# SCHematic_wetterstation_1_2021-12-09.net
KiCad netlist of a schematic drawn in EasyEDA
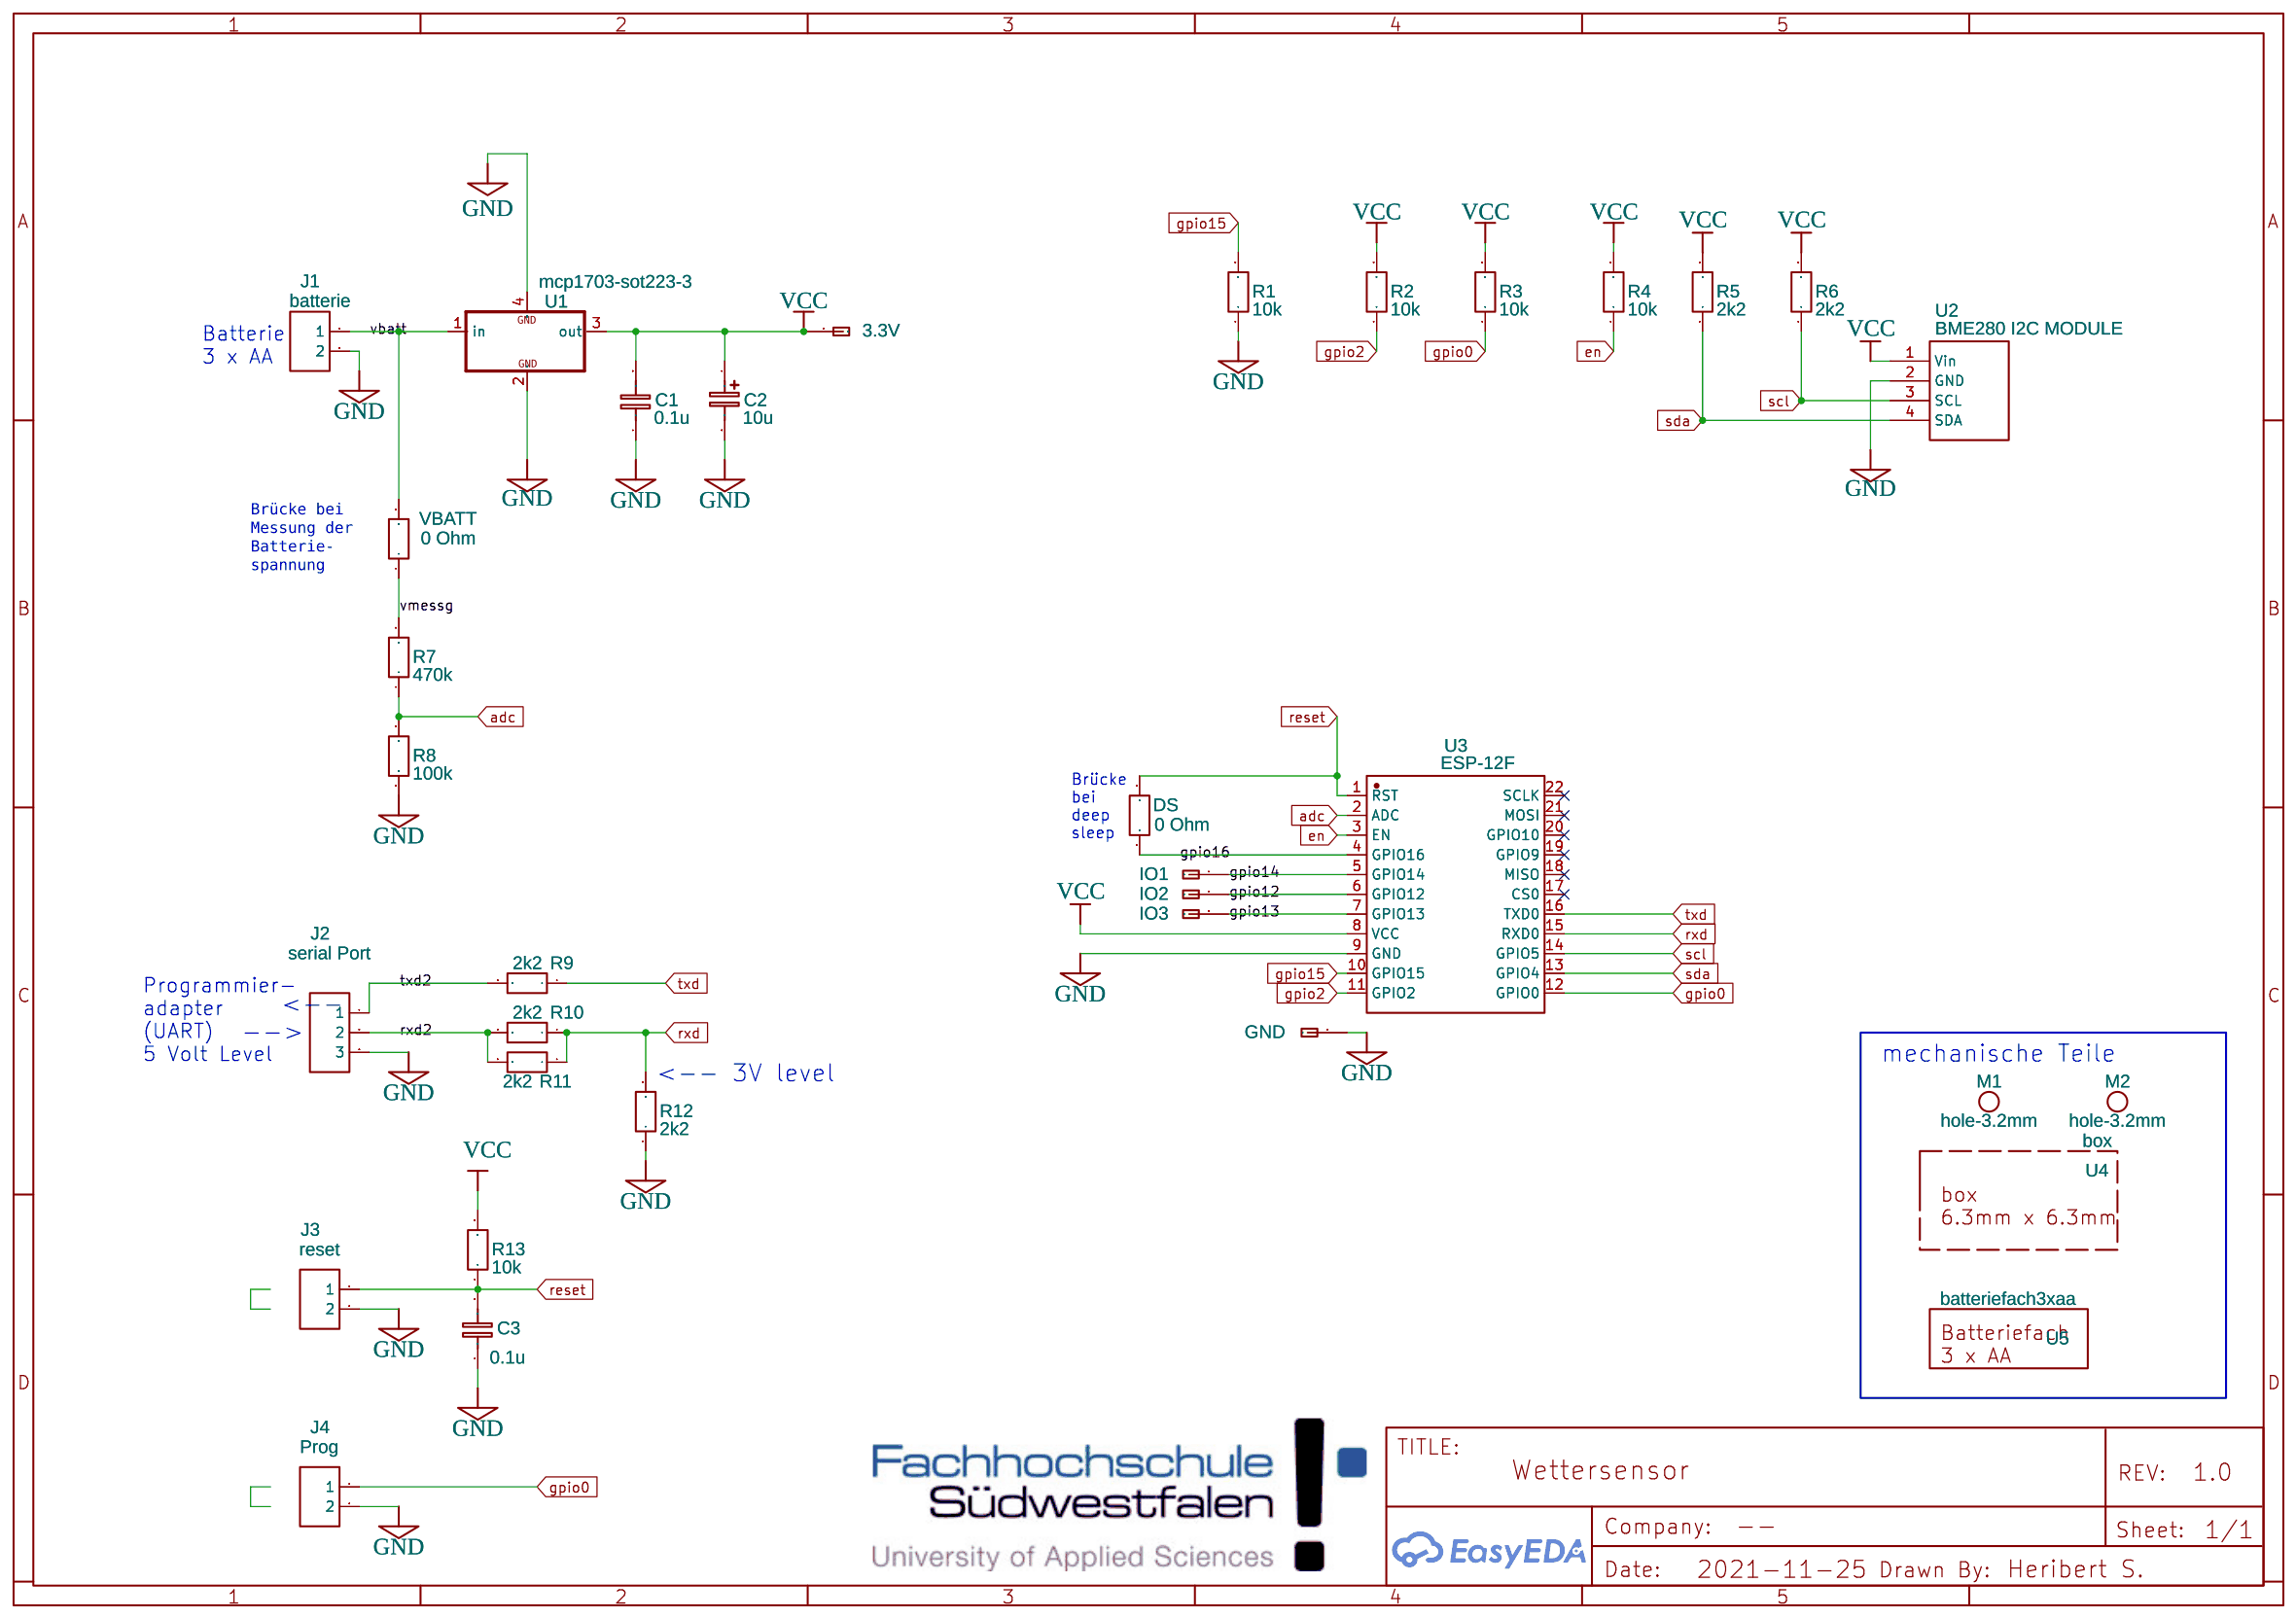
[diagram p0: schematic sheet]

(export (version "E")
  (design (tool "Eeschema 10.0.6"))
  (components
    (comp (ref "3.3V") (value "smdPad") (libsource (lib "") (part "smdPad_2")))
    (comp (ref "C1") (value "0.1u") (libsource (lib "") (part "C_0603_EU")))
    (comp (ref "C2") (value "10u") (libsource (lib "") (part "C_Tan_SMD_A_EU")))
    (comp (ref "C3") (value "0.1u") (libsource (lib "") (part "C_0603_EU_1")))
    (comp (ref "DS") (value "0 Ohm") (libsource (lib "") (part "R_0805_EU_3")))
    (comp (ref "GND") (value "smdPad") (libsource (lib "") (part "smdPad_1")))
    (comp (ref "IO1") (value "smdPad") (libsource (lib "") (part "smdPad")))
    (comp (ref "IO2") (value "smdPad") (libsource (lib "") (part "smdPad")))
    (comp (ref "IO3") (value "smdPad") (libsource (lib "") (part "smdPad")))
    (comp (ref "J1")
      (value "batterie")
      (fields (field (name "BOM_Supplier Part") "C124375"))
      (libsource (lib "") (part "HDR-M-2.54_1x2"))
    )
    (comp (ref "J2")
      (value "serial Port")
      (fields (field (name "BOM_Supplier Part") "C180248"))
      (libsource (lib "") (part "HDR-M-2.54_1x3"))
    )
    (comp (ref "J3")
      (value "reset")
      (fields (field (name "BOM_Supplier Part") "C124375"))
      (libsource (lib "") (part "HDR-M-2.54_1x2"))
    )
    (comp (ref "J4")
      (value "Prog")
      (fields (field (name "BOM_Supplier Part") "C124375"))
      (libsource (lib "") (part "HDR-M-2.54_1x2"))
    )
    (comp (ref "M1")
      (value "hole-3.2mm")
      (fields
        (field (name "BOM_Manufacturer Part") "SIN-002T-1.0")
        (field (name "BOM_Supplier Part") "C265414")
      )
      (libsource (lib "") (part "hole-3.2mm"))
    )
    (comp (ref "M2")
      (value "hole-3.2mm")
      (fields
        (field (name "BOM_Manufacturer Part") "SIN-002T-1.0")
        (field (name "BOM_Supplier Part") "C265414")
      )
      (libsource (lib "") (part "hole-3.2mm"))
    )
    (comp (ref "R1") (value "10k") (libsource (lib "") (part "R_0805_EU")))
    (comp (ref "R2") (value "10k") (libsource (lib "") (part "R_0805_EU")))
    (comp (ref "R3") (value "10k") (libsource (lib "") (part "R_0805_EU")))
    (comp (ref "R4") (value "10k") (libsource (lib "") (part "R_0805_EU")))
    (comp (ref "R5") (value "2k2") (libsource (lib "") (part "R_0805_EU")))
    (comp (ref "R6") (value "2k2") (libsource (lib "") (part "R_0805_EU")))
    (comp (ref "R7") (value "470k") (libsource (lib "") (part "R_0805_EU")))
    (comp (ref "R8") (value "100k") (libsource (lib "") (part "R_0805_EU")))
    (comp (ref "R9") (value "2k2") (libsource (lib "") (part "R_0805_EU_2")))
    (comp (ref "R10") (value "2k2") (libsource (lib "") (part "R_0805_EU_2")))
    (comp (ref "R11") (value "2k2") (libsource (lib "") (part "R_0805_EU_2")))
    (comp (ref "R12") (value "2k2") (libsource (lib "") (part "R_0805_EU")))
    (comp (ref "R13") (value "10k") (libsource (lib "") (part "R_0805_EU")))
    (comp (ref "U1")
      (value "mcp1703-sot223-3")
      (fields (field (name "BOM_Supplier Part") "MCP 1703-3302"))
      (libsource (lib "") (part "mcp1703-sot223-3"))
    )
    (comp (ref "U2") (value "BME280 I2C MODULE") (libsource (lib "") (part "BME280 I2C MODULE")))
    (comp (ref "U3")
      (value "ESP-12F")
      (fields
        (field (name "BOM_Manufacturer Part") "ESP-12F(ESP8266MOD)")
        (field (name "BOM_Supplier Part") "C82891")
      )
      (libsource (lib "") (part "ESP-12F(ESP8266MOD)"))
    )
    (comp (ref "U4") (value "box") (libsource (lib "") (part "box")))
    (comp (ref "U5") (value "batteriefach3xaa") (libsource (lib "") (part "batteriefach3xaa")))
    (comp (ref "VBATT") (value "0 Ohm") (libsource (lib "") (part "R_0805_EU_1")))
  )
  (nets
    (net (code "1") (name "/gpio12") (class "Default")
      (node (ref "IO2") (pin "1") (pinfunction "1_1") (pintype "unspecified"))
      (node (ref "U3") (pin "6") (pinfunction "GPIO12_6") (pintype "unspecified"))
    )
    (net (code "2") (name "/gpio13") (class "Default")
      (node (ref "IO3") (pin "1") (pinfunction "1_1") (pintype "unspecified"))
      (node (ref "U3") (pin "7") (pinfunction "GPIO13_7") (pintype "unspecified"))
    )
    (net (code "3") (name "/gpio14") (class "Default")
      (node (ref "IO1") (pin "1") (pinfunction "1_1") (pintype "unspecified"))
      (node (ref "U3") (pin "5") (pinfunction "GPIO14_5") (pintype "unspecified"))
    )
    (net (code "4") (name "/gpio16") (class "Default")
      (node (ref "DS") (pin "1") (pinfunction "1_1") (pintype "unspecified"))
      (node (ref "U3") (pin "4") (pinfunction "GPIO16_4") (pintype "unspecified"))
    )
    (net (code "5") (name "/rxd2") (class "Default")
      (node (ref "J2") (pin "2") (pinfunction "2_2") (pintype "input"))
      (node (ref "R10") (pin "2") (pinfunction "2_2") (pintype "unspecified"))
      (node (ref "R11") (pin "2") (pinfunction "2_2") (pintype "unspecified"))
    )
    (net (code "6") (name "/txd2") (class "Default")
      (node (ref "J2") (pin "1") (pinfunction "1_1") (pintype "input"))
      (node (ref "R9") (pin "2") (pinfunction "2_2") (pintype "unspecified"))
    )
    (net (code "7") (name "/vbatt") (class "Default")
      (node (ref "J1") (pin "1") (pinfunction "1_1") (pintype "unspecified"))
      (node (ref "U1") (pin "1") (pinfunction "in_1") (pintype "bidirectional"))
      (node (ref "VBATT") (pin "2") (pinfunction "2_2") (pintype "unspecified"))
    )
    (net (code "8") (name "/vmessg") (class "Default")
      (node (ref "R7") (pin "2") (pinfunction "2_2") (pintype "unspecified"))
      (node (ref "VBATT") (pin "1") (pinfunction "1_1") (pintype "unspecified"))
    )
    (net (code "9") (name "GND") (class "Default")
      (node (ref "C1") (pin "1") (pinfunction "1_1") (pintype "unspecified"))
      (node (ref "C2") (pin "2") (pinfunction "2_2") (pintype "unspecified"))
      (node (ref "C3") (pin "1") (pinfunction "1_1") (pintype "unspecified"))
      (node (ref "GND") (pin "1") (pinfunction "1_1") (pintype "unspecified"))
      (node (ref "J1") (pin "2") (pinfunction "2_2") (pintype "unspecified"))
      (node (ref "J2") (pin "3") (pinfunction "3_3") (pintype "input"))
      (node (ref "J3") (pin "2") (pinfunction "2_2") (pintype "unspecified"))
      (node (ref "J4") (pin "2") (pinfunction "2_2") (pintype "unspecified"))
      (node (ref "R1") (pin "1") (pinfunction "1_1") (pintype "unspecified"))
      (node (ref "R12") (pin "1") (pinfunction "1_1") (pintype "unspecified"))
      (node (ref "R8") (pin "1") (pinfunction "1_1") (pintype "unspecified"))
      (node (ref "U1") (pin "2") (pinfunction "GND_2") (pintype "bidirectional"))
      (node (ref "U1") (pin "4") (pinfunction "GND_4") (pintype "bidirectional"))
      (node (ref "U2") (pin "2") (pinfunction "GND_2") (pintype "unspecified"))
      (node (ref "U3") (pin "9") (pinfunction "GND_9") (pintype "unspecified"))
    )
    (net (code "10") (name "VCC") (class "Default")
      (node (ref "3.3V") (pin "1") (pinfunction "1_1") (pintype "unspecified"))
      (node (ref "C1") (pin "2") (pinfunction "2_2") (pintype "unspecified"))
      (node (ref "C2") (pin "1") (pinfunction "1_1") (pintype "unspecified"))
      (node (ref "R13") (pin "2") (pinfunction "2_2") (pintype "unspecified"))
      (node (ref "R2") (pin "2") (pinfunction "2_2") (pintype "unspecified"))
      (node (ref "R3") (pin "2") (pinfunction "2_2") (pintype "unspecified"))
      (node (ref "R4") (pin "2") (pinfunction "2_2") (pintype "unspecified"))
      (node (ref "R5") (pin "2") (pinfunction "2_2") (pintype "unspecified"))
      (node (ref "R6") (pin "2") (pinfunction "2_2") (pintype "unspecified"))
      (node (ref "U1") (pin "3") (pinfunction "out_3") (pintype "bidirectional"))
      (node (ref "U2") (pin "1") (pinfunction "Vin_1") (pintype "unspecified"))
      (node (ref "U3") (pin "8") (pinfunction "VCC_8") (pintype "unspecified"))
    )
    (net (code "11") (name "adc") (class "Default")
      (node (ref "R7") (pin "1") (pinfunction "1_1") (pintype "unspecified"))
      (node (ref "R8") (pin "2") (pinfunction "2_2") (pintype "unspecified"))
      (node (ref "U3") (pin "2") (pinfunction "ADC_2") (pintype "unspecified"))
    )
    (net (code "12") (name "en") (class "Default")
      (node (ref "R4") (pin "1") (pinfunction "1_1") (pintype "unspecified"))
      (node (ref "U3") (pin "3") (pinfunction "EN_3") (pintype "unspecified"))
    )
    (net (code "13") (name "gpio0") (class "Default")
      (node (ref "J4") (pin "1") (pinfunction "1_1") (pintype "unspecified"))
      (node (ref "R3") (pin "1") (pinfunction "1_1") (pintype "unspecified"))
      (node (ref "U3") (pin "12") (pinfunction "GPIO0_12") (pintype "unspecified"))
    )
    (net (code "14") (name "gpio2") (class "Default")
      (node (ref "R2") (pin "1") (pinfunction "1_1") (pintype "unspecified"))
      (node (ref "U3") (pin "11") (pinfunction "GPIO2_11") (pintype "unspecified"))
    )
    (net (code "15") (name "gpio15") (class "Default")
      (node (ref "R1") (pin "2") (pinfunction "2_2") (pintype "unspecified"))
      (node (ref "U3") (pin "10") (pinfunction "GPIO15_10") (pintype "unspecified"))
    )
    (net (code "16") (name "reset") (class "Default")
      (node (ref "C3") (pin "2") (pinfunction "2_2") (pintype "unspecified"))
      (node (ref "DS") (pin "2") (pinfunction "2_2") (pintype "unspecified"))
      (node (ref "J3") (pin "1") (pinfunction "1_1") (pintype "unspecified"))
      (node (ref "R13") (pin "1") (pinfunction "1_1") (pintype "unspecified"))
      (node (ref "U3") (pin "1") (pinfunction "RST_1") (pintype "unspecified"))
    )
    (net (code "17") (name "rxd") (class "Default")
      (node (ref "R10") (pin "1") (pinfunction "1_1") (pintype "unspecified"))
      (node (ref "R11") (pin "1") (pinfunction "1_1") (pintype "unspecified"))
      (node (ref "R12") (pin "2") (pinfunction "2_2") (pintype "unspecified"))
      (node (ref "U3") (pin "15") (pinfunction "RXD0_15") (pintype "unspecified"))
    )
    (net (code "18") (name "scl") (class "Default")
      (node (ref "R6") (pin "1") (pinfunction "1_1") (pintype "unspecified"))
      (node (ref "U2") (pin "3") (pinfunction "SCL_3") (pintype "unspecified"))
      (node (ref "U3") (pin "14") (pinfunction "GPIO5_14") (pintype "unspecified"))
    )
    (net (code "19") (name "sda") (class "Default")
      (node (ref "R5") (pin "1") (pinfunction "1_1") (pintype "unspecified"))
      (node (ref "U2") (pin "4") (pinfunction "SDA_4") (pintype "unspecified"))
      (node (ref "U3") (pin "13") (pinfunction "GPIO4_13") (pintype "unspecified"))
    )
    (net (code "20") (name "txd") (class "Default")
      (node (ref "R9") (pin "1") (pinfunction "1_1") (pintype "unspecified"))
      (node (ref "U3") (pin "16") (pinfunction "TXD0_16") (pintype "unspecified"))
    )
    (net (code "21") (name "unconnected-(U3-CS0-Pad17)") (class "Default")
      (node (ref "U3") (pin "17") (pinfunction "CS0_17") (pintype "unspecified+no_connect"))
    )
    (net (code "22") (name "unconnected-(U3-GPIO9-Pad19)") (class "Default")
      (node (ref "U3") (pin "19") (pinfunction "GPIO9_19") (pintype "unspecified+no_connect"))
    )
    (net (code "23") (name "unconnected-(U3-GPIO10-Pad20)") (class "Default")
      (node (ref "U3") (pin "20") (pinfunction "GPIO10_20") (pintype "unspecified+no_connect"))
    )
    (net (code "24") (name "unconnected-(U3-MISO-Pad18)") (class "Default")
      (node (ref "U3") (pin "18") (pinfunction "MISO_18") (pintype "unspecified+no_connect"))
    )
    (net (code "25") (name "unconnected-(U3-MOSI-Pad21)") (class "Default")
      (node (ref "U3") (pin "21") (pinfunction "MOSI_21") (pintype "unspecified+no_connect"))
    )
    (net (code "26") (name "unconnected-(U3-SCLK-Pad22)") (class "Default")
      (node (ref "U3") (pin "22") (pinfunction "SCLK_22") (pintype "unspecified+no_connect"))
    )
  )
)
